# Anchor_PCB_V1.net
KiCad netlist of a schematic drawn in EAGLE
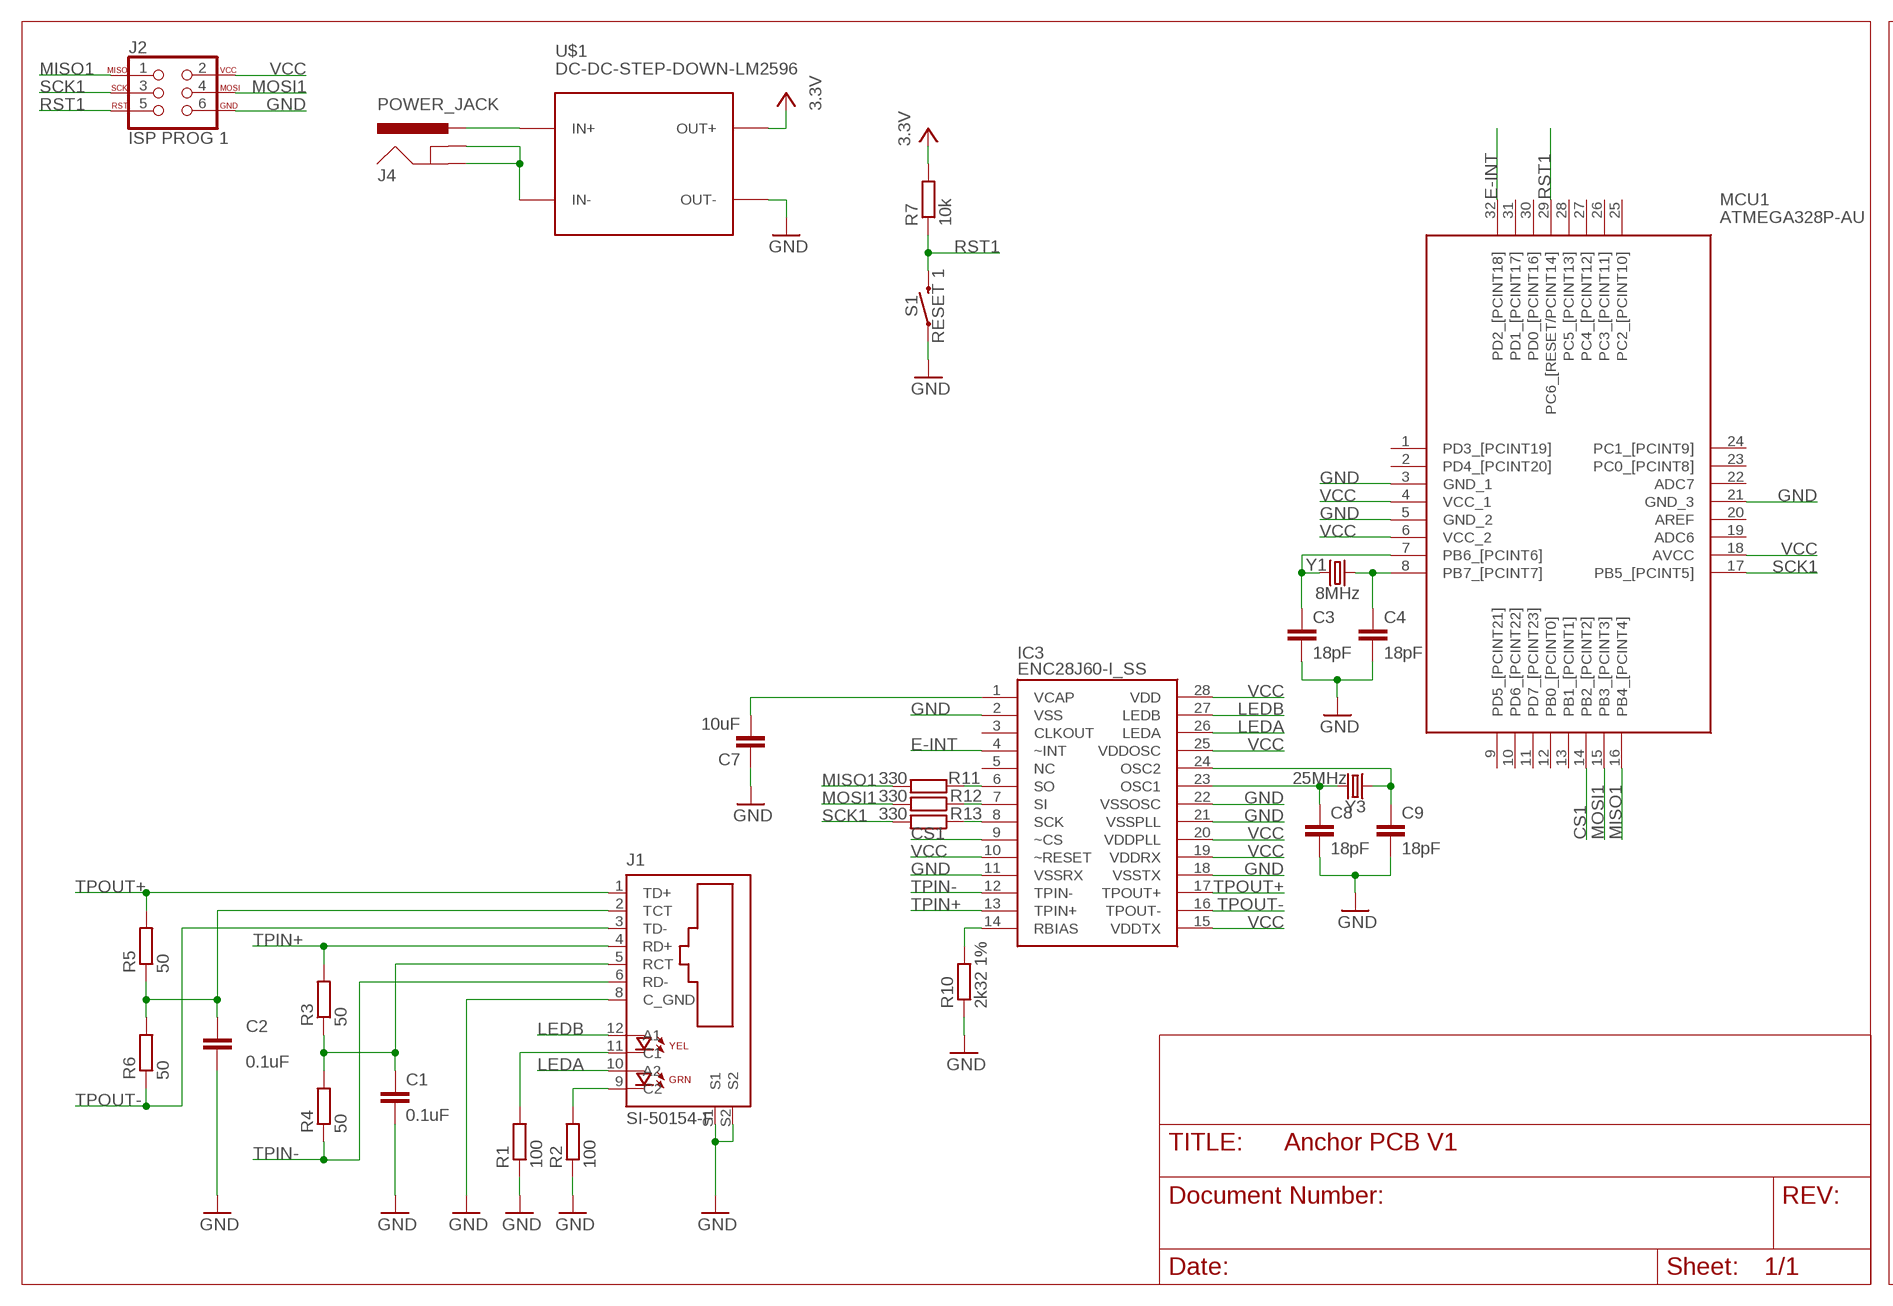
[diagram p0: schematic, sheet 1, part 1 of 2]
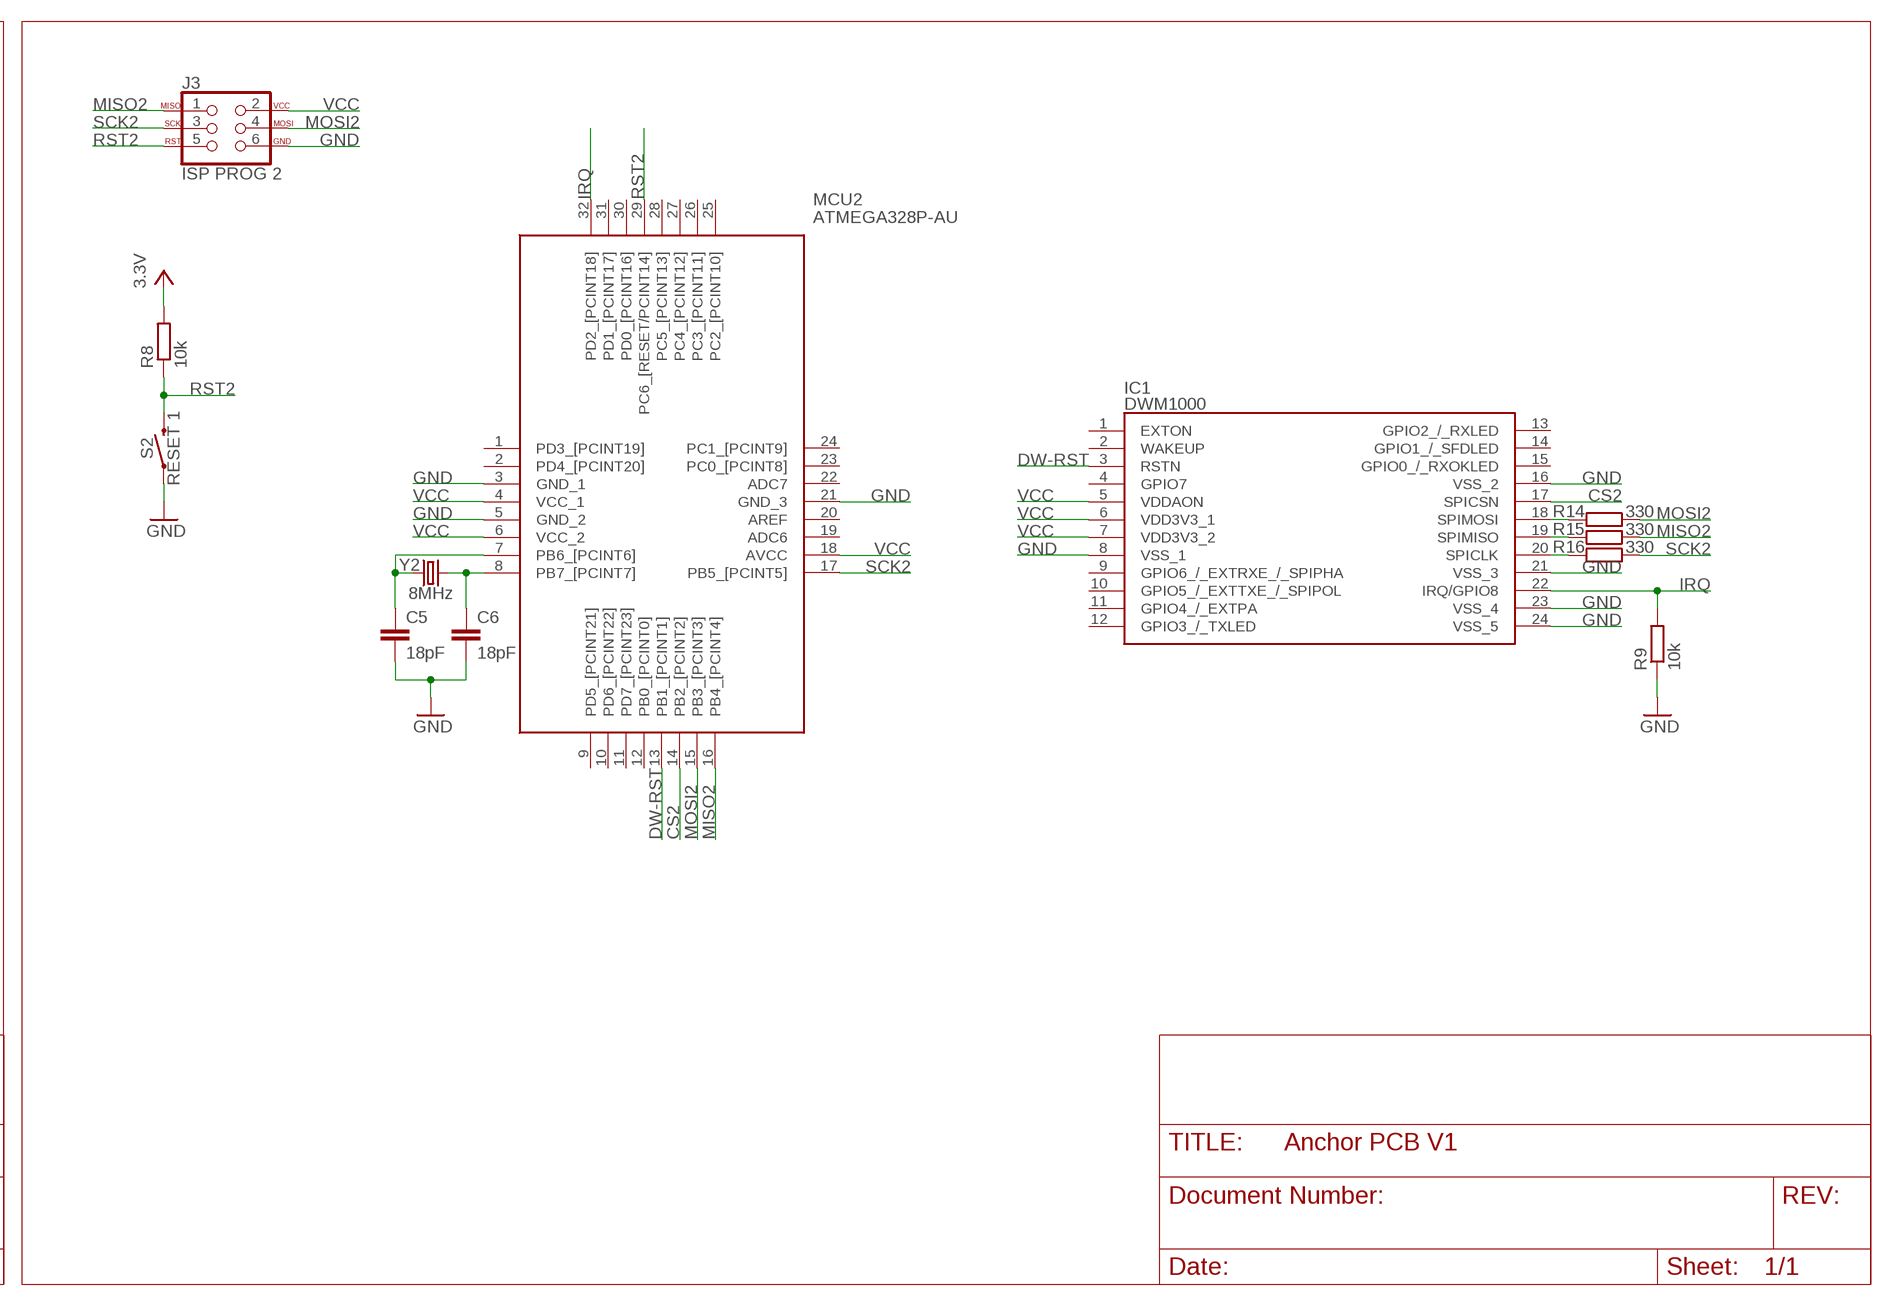
[diagram p1: schematic, sheet 1, part 2 of 2]

(export (version "E")
  (design (tool "Eeschema 10.0.6"))
  (components
    (comp (ref "C1")
      (value "0.1uF")
      (footprint "eagle-import:C1206")
      (libsource (lib "eagle-import") (part "C-EUC1206"))
    )
    (comp (ref "C2")
      (value "0.1uF")
      (footprint "eagle-import:C1206")
      (libsource (lib "eagle-import") (part "C-EUC1206"))
    )
    (comp (ref "C3")
      (value "18pF")
      (footprint "eagle-import:C1206")
      (libsource (lib "eagle-import") (part "C-EUC1206"))
    )
    (comp (ref "C4")
      (value "18pF")
      (footprint "eagle-import:C1206")
      (libsource (lib "eagle-import") (part "C-EUC1206"))
    )
    (comp (ref "C5")
      (value "18pF")
      (footprint "eagle-import:C1206")
      (libsource (lib "eagle-import") (part "C-EUC1206"))
    )
    (comp (ref "C6")
      (value "18pF")
      (footprint "eagle-import:C1206")
      (libsource (lib "eagle-import") (part "C-EUC1206"))
    )
    (comp (ref "C7")
      (value "10uF")
      (footprint "eagle-import:C1206")
      (libsource (lib "eagle-import") (part "C-EUC1206"))
    )
    (comp (ref "C8")
      (value "18pF")
      (footprint "eagle-import:C1206")
      (libsource (lib "eagle-import") (part "C-EUC1206"))
    )
    (comp (ref "C9")
      (value "18pF")
      (footprint "eagle-import:C1206")
      (libsource (lib "eagle-import") (part "C-EUC1206"))
    )
    (comp (ref "IC1")
      (value "DWM1000")
      (footprint "eagle-import:DWM1000")
      (libsource (lib "eagle-import") (part "DWM1000"))
    )
    (comp (ref "IC3")
      (value "ENC28J60-I_SS")
      (footprint "eagle-import:SOP65P780X200-28N")
      (fields (field (name "ARROW_PART_NUMBER") "ENC28J60-I/SS") (field (name "RS_PART_NUMBER") "7707755P"))
      (libsource (lib "eagle-import") (part "ENC28J60-I_SS"))
    )
    (comp (ref "J1")
      (value "SI-50154-F")
      (footprint "eagle-import:STEWART_SI-50154-F")
      (fields (field (name "MF") "Stewart Connector"))
      (libsource (lib "eagle-import") (part "SI-50154-F"))
    )
    (comp (ref "J2")
      (value "ISP PROG 1")
      (footprint "eagle-import:2X3")
      (libsource (lib "eagle-import") (part "AVR_SPI_PROG_3X2PTH"))
    )
    (comp (ref "J3")
      (value "ISP PROG 2")
      (footprint "eagle-import:2X3")
      (libsource (lib "eagle-import") (part "AVR_SPI_PROG_3X2PTH"))
    )
    (comp (ref "J4")
      (value "POWER_JACK")
      (footprint "eagle-import:POWER_JACK_PTH")
      (libsource (lib "eagle-import") (part "POWER_JACK"))
    )
    (comp (ref "MCU1")
      (value "ATMEGA328P-AU")
      (footprint "eagle-import:QFP80P900X900X120-32N")
      (fields (field (name "RS_PART_NUMBER") "1310271"))
      (libsource (lib "eagle-import") (part "ATMEGA328P-AU"))
    )
    (comp (ref "MCU2")
      (value "ATMEGA328P-AU")
      (footprint "eagle-import:QFP80P900X900X120-32N")
      (fields (field (name "RS_PART_NUMBER") "1310271"))
      (libsource (lib "eagle-import") (part "ATMEGA328P-AU"))
    )
    (comp (ref "R1")
      (value "100")
      (footprint "eagle-import:R1206")
      (libsource (lib "eagle-import") (part "R-EU_R1206"))
    )
    (comp (ref "R2")
      (value "100")
      (footprint "eagle-import:R1206")
      (libsource (lib "eagle-import") (part "R-EU_R1206"))
    )
    (comp (ref "R3")
      (value "50")
      (footprint "eagle-import:R1206")
      (libsource (lib "eagle-import") (part "R-EU_R1206"))
    )
    (comp (ref "R4")
      (value "50")
      (footprint "eagle-import:R1206")
      (libsource (lib "eagle-import") (part "R-EU_R1206"))
    )
    (comp (ref "R5")
      (value "50")
      (footprint "eagle-import:R1206")
      (libsource (lib "eagle-import") (part "R-EU_R1206"))
    )
    (comp (ref "R6")
      (value "50")
      (footprint "eagle-import:R1206")
      (libsource (lib "eagle-import") (part "R-EU_R1206"))
    )
    (comp (ref "R7")
      (value "10k")
      (footprint "eagle-import:R1206")
      (libsource (lib "eagle-import") (part "R-EU_R1206"))
    )
    (comp (ref "R8")
      (value "10k")
      (footprint "eagle-import:R1206")
      (libsource (lib "eagle-import") (part "R-EU_R1206"))
    )
    (comp (ref "R9")
      (value "10k")
      (footprint "eagle-import:R1206")
      (libsource (lib "eagle-import") (part "R-EU_R1206"))
    )
    (comp (ref "R10")
      (value "2k32 1%")
      (footprint "eagle-import:R1206")
      (libsource (lib "eagle-import") (part "R-EU_R1206"))
    )
    (comp (ref "R11")
      (value "330")
      (footprint "eagle-import:R1206")
      (libsource (lib "eagle-import") (part "R-EU_R1206"))
    )
    (comp (ref "R12")
      (value "330")
      (footprint "eagle-import:R1206")
      (libsource (lib "eagle-import") (part "R-EU_R1206"))
    )
    (comp (ref "R13")
      (value "330")
      (footprint "eagle-import:R1206")
      (libsource (lib "eagle-import") (part "R-EU_R1206"))
    )
    (comp (ref "R14")
      (value "330")
      (footprint "eagle-import:R1206")
      (libsource (lib "eagle-import") (part "R-EU_R1206"))
    )
    (comp (ref "R15")
      (value "330")
      (footprint "eagle-import:R1206")
      (libsource (lib "eagle-import") (part "R-EU_R1206"))
    )
    (comp (ref "R16")
      (value "330")
      (footprint "eagle-import:R1206")
      (libsource (lib "eagle-import") (part "R-EU_R1206"))
    )
    (comp (ref "S1")
      (value "RESET 1")
      (footprint "eagle-import:TACTILE_SWITCH_PTH_6.0MM")
      (libsource (lib "eagle-import") (part "MOMENTARY-SWITCH-SPST-PTH-6.0MM"))
    )
    (comp (ref "S2")
      (value "RESET 1")
      (footprint "eagle-import:TACTILE_SWITCH_PTH_6.0MM")
      (libsource (lib "eagle-import") (part "MOMENTARY-SWITCH-SPST-PTH-6.0MM"))
    )
    (comp (ref "U$1")
      (value "DC-DC-STEP-DOWN-LM2596")
      (footprint "eagle-import:DC-DC-STEP-DOWN-LM2596")
      (libsource (lib "eagle-import") (part "DC-DC-STEP-DOWN-LM2596"))
    )
    (comp (ref "Y1")
      (value "8MHz")
      (footprint "eagle-import:HC49US")
      (libsource (lib "eagle-import") (part "CRYSTALPTH-HC49US"))
    )
    (comp (ref "Y2")
      (value "8MHz")
      (footprint "eagle-import:HC49US")
      (libsource (lib "eagle-import") (part "CRYSTALPTH-HC49US"))
    )
    (comp (ref "Y3")
      (value "25MHz")
      (footprint "eagle-import:HC49US")
      (libsource (lib "eagle-import") (part "CRYSTALPTH-HC49US"))
    )
  )
  (nets
    (net (code "1") (name "/CS1") (class "Default")
      (node (ref "IC3") (pin "9") (pinfunction "~{CS}_9") (pintype "bidirectional"))
      (node (ref "MCU1") (pin "14") (pinfunction "PB2_[PCINT2]_14") (pintype "bidirectional"))
    )
    (net (code "2") (name "/CS2") (class "Default")
      (node (ref "IC1") (pin "17") (pinfunction "SPICSN_17") (pintype "bidirectional"))
      (node (ref "MCU2") (pin "14") (pinfunction "PB2_[PCINT2]_14") (pintype "bidirectional"))
    )
    (net (code "3") (name "/DW-RST") (class "Default")
      (node (ref "IC1") (pin "3") (pinfunction "RSTN_3") (pintype "bidirectional"))
      (node (ref "MCU2") (pin "13") (pinfunction "PB1_[PCINT1]_13") (pintype "bidirectional"))
    )
    (net (code "4") (name "/E-INT") (class "Default")
      (node (ref "IC3") (pin "4") (pinfunction "~{INT}_4") (pintype "bidirectional"))
      (node (ref "MCU1") (pin "32") (pinfunction "PD2_[PCINT18]_32") (pintype "bidirectional"))
    )
    (net (code "5") (name "/IRQ") (class "Default")
      (node (ref "IC1") (pin "22") (pinfunction "IRQ/GPIO8_22") (pintype "bidirectional"))
      (node (ref "MCU2") (pin "32") (pinfunction "PD2_[PCINT18]_32") (pintype "bidirectional"))
      (node (ref "R9") (pin "2") (pinfunction "2_2") (pintype "passive"))
    )
    (net (code "6") (name "/LEDA") (class "Default")
      (node (ref "IC3") (pin "26") (pinfunction "LEDA_26") (pintype "bidirectional"))
      (node (ref "J1") (pin "10") (pinfunction "A2_10") (pintype "passive"))
    )
    (net (code "7") (name "/LEDB") (class "Default")
      (node (ref "IC3") (pin "27") (pinfunction "LEDB_27") (pintype "bidirectional"))
      (node (ref "J1") (pin "12") (pinfunction "A1_12") (pintype "passive"))
    )
    (net (code "8") (name "/MISO1") (class "Default")
      (node (ref "J2") (pin "1") (pinfunction "1_1") (pintype "passive"))
      (node (ref "MCU1") (pin "16") (pinfunction "PB4_[PCINT4]_16") (pintype "bidirectional"))
      (node (ref "R11") (pin "2") (pinfunction "2_2") (pintype "passive"))
    )
    (net (code "9") (name "/MISO2") (class "Default")
      (node (ref "J3") (pin "1") (pinfunction "1_1") (pintype "passive"))
      (node (ref "MCU2") (pin "16") (pinfunction "PB4_[PCINT4]_16") (pintype "bidirectional"))
      (node (ref "R15") (pin "1") (pinfunction "1_1") (pintype "passive"))
    )
    (net (code "10") (name "/MOSI1") (class "Default")
      (node (ref "J2") (pin "4") (pinfunction "4_4") (pintype "passive"))
      (node (ref "MCU1") (pin "15") (pinfunction "PB3_[PCINT3]_15") (pintype "bidirectional"))
      (node (ref "R12") (pin "2") (pinfunction "2_2") (pintype "passive"))
    )
    (net (code "11") (name "/MOSI2") (class "Default")
      (node (ref "J3") (pin "4") (pinfunction "4_4") (pintype "passive"))
      (node (ref "MCU2") (pin "15") (pinfunction "PB3_[PCINT3]_15") (pintype "bidirectional"))
      (node (ref "R14") (pin "1") (pinfunction "1_1") (pintype "passive"))
    )
    (net (code "12") (name "/RST1") (class "Default")
      (node (ref "J2") (pin "5") (pinfunction "5_5") (pintype "passive"))
      (node (ref "MCU1") (pin "29") (pinfunction "PC6_[RESET/PCINT14]_29") (pintype "bidirectional"))
      (node (ref "R7") (pin "1") (pinfunction "1_1") (pintype "passive"))
      (node (ref "S1") (pin "3") (pinfunction "2_3") (pintype "passive"))
    )
    (net (code "13") (name "/RST2") (class "Default")
      (node (ref "J3") (pin "5") (pinfunction "5_5") (pintype "passive"))
      (node (ref "MCU2") (pin "29") (pinfunction "PC6_[RESET/PCINT14]_29") (pintype "bidirectional"))
      (node (ref "R8") (pin "1") (pinfunction "1_1") (pintype "passive"))
      (node (ref "S2") (pin "3") (pinfunction "2_3") (pintype "passive"))
    )
    (net (code "14") (name "/SCK1") (class "Default")
      (node (ref "J2") (pin "3") (pinfunction "3_3") (pintype "passive"))
      (node (ref "MCU1") (pin "17") (pinfunction "PB5_[PCINT5]_17") (pintype "bidirectional"))
      (node (ref "R13") (pin "2") (pinfunction "2_2") (pintype "passive"))
    )
    (net (code "15") (name "/SCK2") (class "Default")
      (node (ref "J3") (pin "3") (pinfunction "3_3") (pintype "passive"))
      (node (ref "MCU2") (pin "17") (pinfunction "PB5_[PCINT5]_17") (pintype "bidirectional"))
      (node (ref "R16") (pin "1") (pinfunction "1_1") (pintype "passive"))
    )
    (net (code "16") (name "/TPIN+") (class "Default")
      (node (ref "IC3") (pin "13") (pinfunction "TPIN+_13") (pintype "bidirectional"))
      (node (ref "J1") (pin "4") (pinfunction "RD+_4") (pintype "passive"))
      (node (ref "R3") (pin "2") (pinfunction "2_2") (pintype "passive"))
    )
    (net (code "17") (name "/TPIN-") (class "Default")
      (node (ref "IC3") (pin "12") (pinfunction "TPIN-_12") (pintype "bidirectional"))
      (node (ref "J1") (pin "6") (pinfunction "RD-_6") (pintype "passive"))
      (node (ref "R4") (pin "1") (pinfunction "1_1") (pintype "passive"))
    )
    (net (code "18") (name "/TPOUT+") (class "Default")
      (node (ref "IC3") (pin "17") (pinfunction "TPOUT+_17") (pintype "bidirectional"))
      (node (ref "J1") (pin "1") (pinfunction "TD+_1") (pintype "passive"))
      (node (ref "R5") (pin "2") (pinfunction "2_2") (pintype "passive"))
    )
    (net (code "19") (name "/TPOUT-") (class "Default")
      (node (ref "IC3") (pin "16") (pinfunction "TPOUT-_16") (pintype "bidirectional"))
      (node (ref "J1") (pin "3") (pinfunction "TD-_3") (pintype "passive"))
      (node (ref "R6") (pin "1") (pinfunction "1_1") (pintype "passive"))
    )
    (net (code "20") (name "3.3V") (class "Default")
      (node (ref "IC1") (pin "5") (pinfunction "VDDAON_5") (pintype "bidirectional"))
      (node (ref "IC1") (pin "6") (pinfunction "VDD3V3_1_6") (pintype "bidirectional"))
      (node (ref "IC1") (pin "7") (pinfunction "VDD3V3_2_7") (pintype "bidirectional"))
      (node (ref "IC3") (pin "10") (pinfunction "~{RESET}_10") (pintype "bidirectional"))
      (node (ref "IC3") (pin "15") (pinfunction "VDDTX_15") (pintype "bidirectional"))
      (node (ref "IC3") (pin "19") (pinfunction "VDDRX_19") (pintype "bidirectional"))
      (node (ref "IC3") (pin "20") (pinfunction "VDDPLL_20") (pintype "bidirectional"))
      (node (ref "IC3") (pin "25") (pinfunction "VDDOSC_25") (pintype "bidirectional"))
      (node (ref "IC3") (pin "28") (pinfunction "VDD_28") (pintype "bidirectional"))
      (node (ref "J2") (pin "2") (pinfunction "2_2") (pintype "passive"))
      (node (ref "J3") (pin "2") (pinfunction "2_2") (pintype "passive"))
      (node (ref "MCU1") (pin "18") (pinfunction "AVCC_18") (pintype "power_in"))
      (node (ref "MCU1") (pin "4") (pinfunction "VCC_1_4") (pintype "power_in"))
      (node (ref "MCU1") (pin "6") (pinfunction "VCC_2_6") (pintype "power_in"))
      (node (ref "MCU2") (pin "18") (pinfunction "AVCC_18") (pintype "power_in"))
      (node (ref "MCU2") (pin "4") (pinfunction "VCC_1_4") (pintype "power_in"))
      (node (ref "MCU2") (pin "6") (pinfunction "VCC_2_6") (pintype "power_in"))
      (node (ref "R7") (pin "2") (pinfunction "2_2") (pintype "passive"))
      (node (ref "R8") (pin "2") (pinfunction "2_2") (pintype "passive"))
      (node (ref "U$1") (pin "OUT+") (pinfunction "OUT+_OUT+") (pintype "bidirectional"))
    )
    (net (code "21") (name "GND") (class "Default")
      (node (ref "C1") (pin "2") (pinfunction "2_2") (pintype "passive"))
      (node (ref "C2") (pin "2") (pinfunction "2_2") (pintype "passive"))
      (node (ref "C3") (pin "2") (pinfunction "2_2") (pintype "passive"))
      (node (ref "C4") (pin "2") (pinfunction "2_2") (pintype "passive"))
      (node (ref "C5") (pin "2") (pinfunction "2_2") (pintype "passive"))
      (node (ref "C6") (pin "2") (pinfunction "2_2") (pintype "passive"))
      (node (ref "C7") (pin "1") (pinfunction "1_1") (pintype "passive"))
      (node (ref "C8") (pin "2") (pinfunction "2_2") (pintype "passive"))
      (node (ref "C9") (pin "2") (pinfunction "2_2") (pintype "passive"))
      (node (ref "IC1") (pin "16") (pinfunction "VSS_2_16") (pintype "bidirectional"))
      (node (ref "IC1") (pin "21") (pinfunction "VSS_3_21") (pintype "bidirectional"))
      (node (ref "IC1") (pin "23") (pinfunction "VSS_4_23") (pintype "bidirectional"))
      (node (ref "IC1") (pin "24") (pinfunction "VSS_5_24") (pintype "bidirectional"))
      (node (ref "IC1") (pin "8") (pinfunction "VSS_1_8") (pintype "bidirectional"))
      (node (ref "IC3") (pin "11") (pinfunction "VSSRX_11") (pintype "bidirectional"))
      (node (ref "IC3") (pin "18") (pinfunction "VSSTX_18") (pintype "bidirectional"))
      (node (ref "IC3") (pin "2") (pinfunction "VSS_2") (pintype "bidirectional"))
      (node (ref "IC3") (pin "21") (pinfunction "VSSPLL_21") (pintype "bidirectional"))
      (node (ref "IC3") (pin "22") (pinfunction "VSSOSC_22") (pintype "bidirectional"))
      (node (ref "J1") (pin "8") (pinfunction "C_GND_8") (pintype "passive"))
      (node (ref "J1") (pin "S1") (pinfunction "S1_S1") (pintype "passive"))
      (node (ref "J1") (pin "S2") (pinfunction "S2_S2") (pintype "passive"))
      (node (ref "J2") (pin "6") (pinfunction "6_6") (pintype "passive"))
      (node (ref "J3") (pin "6") (pinfunction "6_6") (pintype "passive"))
      (node (ref "MCU1") (pin "21") (pinfunction "GND_3_21") (pintype "power_in"))
      (node (ref "MCU1") (pin "3") (pinfunction "GND_1_3") (pintype "power_in"))
      (node (ref "MCU1") (pin "5") (pinfunction "GND_2_5") (pintype "power_in"))
      (node (ref "MCU2") (pin "21") (pinfunction "GND_3_21") (pintype "power_in"))
      (node (ref "MCU2") (pin "3") (pinfunction "GND_1_3") (pintype "power_in"))
      (node (ref "MCU2") (pin "5") (pinfunction "GND_2_5") (pintype "power_in"))
      (node (ref "R1") (pin "1") (pinfunction "1_1") (pintype "passive"))
      (node (ref "R10") (pin "1") (pinfunction "1_1") (pintype "passive"))
      (node (ref "R2") (pin "1") (pinfunction "1_1") (pintype "passive"))
      (node (ref "R9") (pin "1") (pinfunction "1_1") (pintype "passive"))
      (node (ref "S1") (pin "1") (pinfunction "1_1") (pintype "passive"))
      (node (ref "S2") (pin "1") (pinfunction "1_1") (pintype "passive"))
      (node (ref "U$1") (pin "OUT-") (pinfunction "OUT-_OUT-") (pintype "bidirectional"))
    )
    (net (code "22") (name "Net-(IC1-SPICLK)") (class "Default")
      (node (ref "IC1") (pin "20") (pinfunction "SPICLK_20") (pintype "bidirectional"))
      (node (ref "R16") (pin "2") (pinfunction "2_2") (pintype "passive"))
    )
    (net (code "23") (name "Net-(IC1-SPIMISO)") (class "Default")
      (node (ref "IC1") (pin "19") (pinfunction "SPIMISO_19") (pintype "bidirectional"))
      (node (ref "R15") (pin "2") (pinfunction "2_2") (pintype "passive"))
    )
    (net (code "24") (name "Net-(IC1-SPIMOSI)") (class "Default")
      (node (ref "IC1") (pin "18") (pinfunction "SPIMOSI_18") (pintype "bidirectional"))
      (node (ref "R14") (pin "2") (pinfunction "2_2") (pintype "passive"))
    )
    (net (code "25") (name "Net-(IC3-OSC1)") (class "Default")
      (node (ref "C8") (pin "1") (pinfunction "1_1") (pintype "passive"))
      (node (ref "IC3") (pin "23") (pinfunction "OSC1_23") (pintype "bidirectional"))
      (node (ref "Y3") (pin "2") (pinfunction "2_2") (pintype "passive"))
    )
    (net (code "26") (name "Net-(IC3-OSC2)") (class "Default")
      (node (ref "C9") (pin "1") (pinfunction "1_1") (pintype "passive"))
      (node (ref "IC3") (pin "24") (pinfunction "OSC2_24") (pintype "bidirectional"))
      (node (ref "Y3") (pin "1") (pinfunction "1_1") (pintype "passive"))
    )
    (net (code "27") (name "Net-(IC3-RBIAS)") (class "Default")
      (node (ref "IC3") (pin "14") (pinfunction "RBIAS_14") (pintype "bidirectional"))
      (node (ref "R10") (pin "2") (pinfunction "2_2") (pintype "passive"))
    )
    (net (code "28") (name "Net-(IC3-SCK)") (class "Default")
      (node (ref "IC3") (pin "8") (pinfunction "SCK_8") (pintype "bidirectional"))
      (node (ref "R13") (pin "1") (pinfunction "1_1") (pintype "passive"))
    )
    (net (code "29") (name "Net-(IC3-SI)") (class "Default")
      (node (ref "IC3") (pin "7") (pinfunction "SI_7") (pintype "bidirectional"))
      (node (ref "R12") (pin "1") (pinfunction "1_1") (pintype "passive"))
    )
    (net (code "30") (name "Net-(IC3-SO)") (class "Default")
      (node (ref "IC3") (pin "6") (pinfunction "SO_6") (pintype "bidirectional"))
      (node (ref "R11") (pin "1") (pinfunction "1_1") (pintype "passive"))
    )
    (net (code "31") (name "Net-(IC3-VCAP)") (class "Default")
      (node (ref "C7") (pin "2") (pinfunction "2_2") (pintype "passive"))
      (node (ref "IC3") (pin "1") (pinfunction "VCAP_1") (pintype "bidirectional"))
    )
    (net (code "32") (name "Net-(J1-C1)") (class "Default")
      (node (ref "J1") (pin "11") (pinfunction "C1_11") (pintype "passive"))
      (node (ref "R1") (pin "2") (pinfunction "2_2") (pintype "passive"))
    )
    (net (code "33") (name "Net-(J1-C2)") (class "Default")
      (node (ref "J1") (pin "9") (pinfunction "C2_9") (pintype "passive"))
      (node (ref "R2") (pin "2") (pinfunction "2_2") (pintype "passive"))
    )
    (net (code "34") (name "Net-(J1-RCT)") (class "Default")
      (node (ref "C1") (pin "1") (pinfunction "1_1") (pintype "passive"))
      (node (ref "J1") (pin "5") (pinfunction "RCT_5") (pintype "passive"))
      (node (ref "R3") (pin "1") (pinfunction "1_1") (pintype "passive"))
      (node (ref "R4") (pin "2") (pinfunction "2_2") (pintype "passive"))
    )
    (net (code "35") (name "Net-(J1-TCT)") (class "Default")
      (node (ref "C2") (pin "1") (pinfunction "1_1") (pintype "passive"))
      (node (ref "J1") (pin "2") (pinfunction "TCT_2") (pintype "passive"))
      (node (ref "R5") (pin "1") (pinfunction "1_1") (pintype "passive"))
      (node (ref "R6") (pin "2") (pinfunction "2_2") (pintype "passive"))
    )
    (net (code "36") (name "Net-(J4-PadGND)") (class "Default")
      (node (ref "J4") (pin "GND") (pinfunction "GND_GND") (pintype "bidirectional"))
      (node (ref "J4") (pin "GNDBREAK") (pinfunction "GNDBREAK_GNDBREAK") (pintype "bidirectional"))
      (node (ref "U$1") (pin "IN-") (pinfunction "IN-_IN-") (pintype "bidirectional"))
    )
    (net (code "37") (name "Net-(J4-PadPWR)") (class "Default")
      (node (ref "J4") (pin "PWR") (pinfunction "PWR_PWR") (pintype "bidirectional"))
      (node (ref "U$1") (pin "IN+") (pinfunction "IN+_IN+") (pintype "bidirectional"))
    )
    (net (code "38") (name "Net-(MCU1-PB6_[PCINT6])") (class "Default")
      (node (ref "C3") (pin "1") (pinfunction "1_1") (pintype "passive"))
      (node (ref "MCU1") (pin "7") (pinfunction "PB6_[PCINT6]_7") (pintype "bidirectional"))
      (node (ref "Y1") (pin "2") (pinfunction "2_2") (pintype "passive"))
    )
    (net (code "39") (name "Net-(MCU1-PB7_[PCINT7])") (class "Default")
      (node (ref "C4") (pin "1") (pinfunction "1_1") (pintype "passive"))
      (node (ref "MCU1") (pin "8") (pinfunction "PB7_[PCINT7]_8") (pintype "bidirectional"))
      (node (ref "Y1") (pin "1") (pinfunction "1_1") (pintype "passive"))
    )
    (net (code "40") (name "Net-(MCU2-PB6_[PCINT6])") (class "Default")
      (node (ref "C5") (pin "1") (pinfunction "1_1") (pintype "passive"))
      (node (ref "MCU2") (pin "7") (pinfunction "PB6_[PCINT6]_7") (pintype "bidirectional"))
      (node (ref "Y2") (pin "1") (pinfunction "1_1") (pintype "passive"))
    )
    (net (code "41") (name "Net-(MCU2-PB7_[PCINT7])") (class "Default")
      (node (ref "C6") (pin "1") (pinfunction "1_1") (pintype "passive"))
      (node (ref "MCU2") (pin "8") (pinfunction "PB7_[PCINT7]_8") (pintype "bidirectional"))
      (node (ref "Y2") (pin "2") (pinfunction "2_2") (pintype "passive"))
    )
    (net (code "42") (name "unconnected-(IC1-EXTON-Pad1)") (class "Default")
      (node (ref "IC1") (pin "1") (pinfunction "EXTON_1") (pintype "bidirectional"))
    )
    (net (code "43") (name "unconnected-(IC1-GPIO0_{slash}_RXOKLED-Pad15)") (class "Default")
      (node (ref "IC1") (pin "15") (pinfunction "GPIO0_/_RXOKLED_15") (pintype "bidirectional"))
    )
    (net (code "44") (name "unconnected-(IC1-GPIO1_{slash}_SFDLED-Pad14)") (class "Default")
      (node (ref "IC1") (pin "14") (pinfunction "GPIO1_/_SFDLED_14") (pintype "bidirectional"))
    )
    (net (code "45") (name "unconnected-(IC1-GPIO2_{slash}_RXLED-Pad13)") (class "Default")
      (node (ref "IC1") (pin "13") (pinfunction "GPIO2_/_RXLED_13") (pintype "bidirectional"))
    )
    (net (code "46") (name "unconnected-(IC1-GPIO3_{slash}_TXLED-Pad12)") (class "Default")
      (node (ref "IC1") (pin "12") (pinfunction "GPIO3_/_TXLED_12") (pintype "bidirectional"))
    )
    (net (code "47") (name "unconnected-(IC1-GPIO4_{slash}_EXTPA-Pad11)") (class "Default")
      (node (ref "IC1") (pin "11") (pinfunction "GPIO4_/_EXTPA_11") (pintype "bidirectional"))
    )
    (net (code "48") (name "unconnected-(IC1-GPIO5_{slash}_EXTTXE_{slash}_SPIPOL-Pad10)") (class "Default")
      (node (ref "IC1") (pin "10") (pinfunction "GPIO5_/_EXTTXE_/_SPIPOL_10") (pintype "bidirectional"))
    )
    (net (code "49") (name "unconnected-(IC1-GPIO6_{slash}_EXTRXE_{slash}_SPIPHA-Pad9)") (class "Default")
      (node (ref "IC1") (pin "9") (pinfunction "GPIO6_/_EXTRXE_/_SPIPHA_9") (pintype "bidirectional"))
    )
    (net (code "50") (name "unconnected-(IC1-GPIO7-Pad4)") (class "Default")
      (node (ref "IC1") (pin "4") (pinfunction "GPIO7_4") (pintype "bidirectional"))
    )
    (net (code "51") (name "unconnected-(IC1-WAKEUP-Pad2)") (class "Default")
      (node (ref "IC1") (pin "2") (pinfunction "WAKEUP_2") (pintype "bidirectional"))
    )
    (net (code "52") (name "unconnected-(IC3-CLKOUT-Pad3)") (class "Default")
      (node (ref "IC3") (pin "3") (pinfunction "CLKOUT_3") (pintype "bidirectional"))
    )
    (net (code "53") (name "unconnected-(IC3-NC-Pad5)") (class "Default")
      (node (ref "IC3") (pin "5") (pinfunction "NC_5") (pintype "no_connect"))
    )
    (net (code "54") (name "unconnected-(MCU1-ADC6-Pad19)") (class "Default")
      (node (ref "MCU1") (pin "19") (pinfunction "ADC6_19") (pintype "bidirectional"))
    )
    (net (code "55") (name "unconnected-(MCU1-ADC7-Pad22)") (class "Default")
      (node (ref "MCU1") (pin "22") (pinfunction "ADC7_22") (pintype "bidirectional"))
    )
    (net (code "56") (name "unconnected-(MCU1-AREF-Pad20)") (class "Default")
      (node (ref "MCU1") (pin "20") (pinfunction "AREF_20") (pintype "bidirectional"))
    )
    (net (code "57") (name "unconnected-(MCU1-PB0_[PCINT0]-Pad12)") (class "Default")
      (node (ref "MCU1") (pin "12") (pinfunction "PB0_[PCINT0]_12") (pintype "bidirectional"))
    )
    (net (code "58") (name "unconnected-(MCU1-PB1_[PCINT1]-Pad13)") (class "Default")
      (node (ref "MCU1") (pin "13") (pinfunction "PB1_[PCINT1]_13") (pintype "bidirectional"))
    )
    (net (code "59") (name "unconnected-(MCU1-PC0_[PCINT8]-Pad23)") (class "Default")
      (node (ref "MCU1") (pin "23") (pinfunction "PC0_[PCINT8]_23") (pintype "bidirectional"))
    )
    (net (code "60") (name "unconnected-(MCU1-PC1_[PCINT9]-Pad24)") (class "Default")
      (node (ref "MCU1") (pin "24") (pinfunction "PC1_[PCINT9]_24") (pintype "bidirectional"))
    )
    (net (code "61") (name "unconnected-(MCU1-PC2_[PCINT10]-Pad25)") (class "Default")
      (node (ref "MCU1") (pin "25") (pinfunction "PC2_[PCINT10]_25") (pintype "bidirectional"))
    )
    (net (code "62") (name "unconnected-(MCU1-PC3_[PCINT11]-Pad26)") (class "Default")
      (node (ref "MCU1") (pin "26") (pinfunction "PC3_[PCINT11]_26") (pintype "bidirectional"))
    )
    (net (code "63") (name "unconnected-(MCU1-PC4_[PCINT12]-Pad27)") (class "Default")
      (node (ref "MCU1") (pin "27") (pinfunction "PC4_[PCINT12]_27") (pintype "bidirectional"))
    )
    (net (code "64") (name "unconnected-(MCU1-PC5_[PCINT13]-Pad28)") (class "Default")
      (node (ref "MCU1") (pin "28") (pinfunction "PC5_[PCINT13]_28") (pintype "bidirectional"))
    )
    (net (code "65") (name "unconnected-(MCU1-PD0_[PCINT16]-Pad30)") (class "Default")
      (node (ref "MCU1") (pin "30") (pinfunction "PD0_[PCINT16]_30") (pintype "bidirectional"))
    )
    (net (code "66") (name "unconnected-(MCU1-PD1_[PCINT17]-Pad31)") (class "Default")
      (node (ref "MCU1") (pin "31") (pinfunction "PD1_[PCINT17]_31") (pintype "bidirectional"))
    )
    (net (code "67") (name "unconnected-(MCU1-PD3_[PCINT19]-Pad1)") (class "Default")
      (node (ref "MCU1") (pin "1") (pinfunction "PD3_[PCINT19]_1") (pintype "bidirectional"))
    )
    (net (code "68") (name "unconnected-(MCU1-PD4_[PCINT20]-Pad2)") (class "Default")
      (node (ref "MCU1") (pin "2") (pinfunction "PD4_[PCINT20]_2") (pintype "bidirectional"))
    )
    (net (code "69") (name "unconnected-(MCU1-PD5_[PCINT21]-Pad9)") (class "Default")
      (node (ref "MCU1") (pin "9") (pinfunction "PD5_[PCINT21]_9") (pintype "bidirectional"))
    )
    (net (code "70") (name "unconnected-(MCU1-PD6_[PCINT22]-Pad10)") (class "Default")
      (node (ref "MCU1") (pin "10") (pinfunction "PD6_[PCINT22]_10") (pintype "bidirectional"))
    )
    (net (code "71") (name "unconnected-(MCU1-PD7_[PCINT23]-Pad11)") (class "Default")
      (node (ref "MCU1") (pin "11") (pinfunction "PD7_[PCINT23]_11") (pintype "bidirectional"))
    )
    (net (code "72") (name "unconnected-(MCU2-ADC6-Pad19)") (class "Default")
      (node (ref "MCU2") (pin "19") (pinfunction "ADC6_19") (pintype "bidirectional"))
    )
    (net (code "73") (name "unconnected-(MCU2-ADC7-Pad22)") (class "Default")
      (node (ref "MCU2") (pin "22") (pinfunction "ADC7_22") (pintype "bidirectional"))
    )
    (net (code "74") (name "unconnected-(MCU2-AREF-Pad20)") (class "Default")
      (node (ref "MCU2") (pin "20") (pinfunction "AREF_20") (pintype "bidirectional"))
    )
    (net (code "75") (name "unconnected-(MCU2-PB0_[PCINT0]-Pad12)") (class "Default")
      (node (ref "MCU2") (pin "12") (pinfunction "PB0_[PCINT0]_12") (pintype "bidirectional"))
    )
    (net (code "76") (name "unconnected-(MCU2-PC0_[PCINT8]-Pad23)") (class "Default")
      (node (ref "MCU2") (pin "23") (pinfunction "PC0_[PCINT8]_23") (pintype "bidirectional"))
    )
    (net (code "77") (name "unconnected-(MCU2-PC1_[PCINT9]-Pad24)") (class "Default")
      (node (ref "MCU2") (pin "24") (pinfunction "PC1_[PCINT9]_24") (pintype "bidirectional"))
    )
    (net (code "78") (name "unconnected-(MCU2-PC2_[PCINT10]-Pad25)") (class "Default")
      (node (ref "MCU2") (pin "25") (pinfunction "PC2_[PCINT10]_25") (pintype "bidirectional"))
    )
    (net (code "79") (name "unconnected-(MCU2-PC3_[PCINT11]-Pad26)") (class "Default")
      (node (ref "MCU2") (pin "26") (pinfunction "PC3_[PCINT11]_26") (pintype "bidirectional"))
    )
    (net (code "80") (name "unconnected-(MCU2-PC4_[PCINT12]-Pad27)") (class "Default")
      (node (ref "MCU2") (pin "27") (pinfunction "PC4_[PCINT12]_27") (pintype "bidirectional"))
    )
    (net (code "81") (name "unconnected-(MCU2-PC5_[PCINT13]-Pad28)") (class "Default")
      (node (ref "MCU2") (pin "28") (pinfunction "PC5_[PCINT13]_28") (pintype "bidirectional"))
    )
    (net (code "82") (name "unconnected-(MCU2-PD0_[PCINT16]-Pad30)") (class "Default")
      (node (ref "MCU2") (pin "30") (pinfunction "PD0_[PCINT16]_30") (pintype "bidirectional"))
    )
    (net (code "83") (name "unconnected-(MCU2-PD1_[PCINT17]-Pad31)") (class "Default")
      (node (ref "MCU2") (pin "31") (pinfunction "PD1_[PCINT17]_31") (pintype "bidirectional"))
    )
    (net (code "84") (name "unconnected-(MCU2-PD3_[PCINT19]-Pad1)") (class "Default")
      (node (ref "MCU2") (pin "1") (pinfunction "PD3_[PCINT19]_1") (pintype "bidirectional"))
    )
    (net (code "85") (name "unconnected-(MCU2-PD4_[PCINT20]-Pad2)") (class "Default")
      (node (ref "MCU2") (pin "2") (pinfunction "PD4_[PCINT20]_2") (pintype "bidirectional"))
    )
    (net (code "86") (name "unconnected-(MCU2-PD5_[PCINT21]-Pad9)") (class "Default")
      (node (ref "MCU2") (pin "9") (pinfunction "PD5_[PCINT21]_9") (pintype "bidirectional"))
    )
    (net (code "87") (name "unconnected-(MCU2-PD6_[PCINT22]-Pad10)") (class "Default")
      (node (ref "MCU2") (pin "10") (pinfunction "PD6_[PCINT22]_10") (pintype "bidirectional"))
    )
    (net (code "88") (name "unconnected-(MCU2-PD7_[PCINT23]-Pad11)") (class "Default")
      (node (ref "MCU2") (pin "11") (pinfunction "PD7_[PCINT23]_11") (pintype "bidirectional"))
    )
  )
)
